# source.net
KiCad netlist of a schematic drawn in Altium Designer
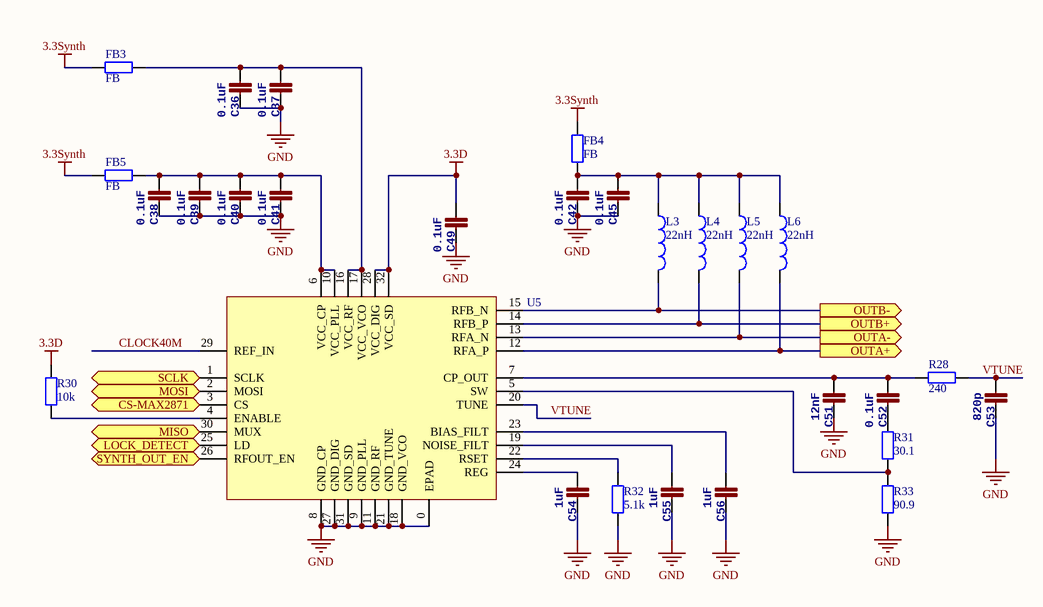
[diagram p0: source.SchDoc]

(export (version "E")
  (design (tool "Eeschema 10.0.6"))
  (components
    (comp (ref "C36")
      (value "0.1uF")
      (footprint "0402")
      (description "<b>Capacitor</b>\nStandard 0603 ceramic capacitor, and 0.1\" leaded capacitor.")
      (fields (field (name "PARTNO") "CC0402ZRY5V7BB104"))
      (libsource (lib "pixhawk2") (part "CAP0402-CAP"))
    )
    (comp (ref "C37")
      (value "0.1uF")
      (footprint "0402")
      (description "<b>Capacitor</b>\nStandard 0603 ceramic capacitor, and 0.1\" leaded capacitor.")
      (fields (field (name "PARTNO") "CC0402ZRY5V7BB104"))
      (libsource (lib "pixhawk2") (part "CAP0402-CAP"))
    )
    (comp (ref "C38")
      (value "0.1uF")
      (footprint "0402")
      (description "<b>Capacitor</b>\nStandard 0603 ceramic capacitor, and 0.1\" leaded capacitor.")
      (fields (field (name "PARTNO") "CC0402ZRY5V7BB104"))
      (libsource (lib "pixhawk2") (part "CAP0402-CAP"))
    )
    (comp (ref "C39")
      (value "0.1uF")
      (footprint "0402")
      (description "<b>Capacitor</b>\nStandard 0603 ceramic capacitor, and 0.1\" leaded capacitor.")
      (fields (field (name "PARTNO") "CC0402ZRY5V7BB104"))
      (libsource (lib "pixhawk2") (part "CAP0402-CAP"))
    )
    (comp (ref "C40")
      (value "0.1uF")
      (footprint "0402")
      (description "<b>Capacitor</b>\nStandard 0603 ceramic capacitor, and 0.1\" leaded capacitor.")
      (fields (field (name "PARTNO") "CC0402ZRY5V7BB104"))
      (libsource (lib "pixhawk2") (part "CAP0402-CAP"))
    )
    (comp (ref "C41")
      (value "0.1uF")
      (footprint "0402")
      (description "<b>Capacitor</b>\nStandard 0603 ceramic capacitor, and 0.1\" leaded capacitor.")
      (fields (field (name "PARTNO") "CC0402ZRY5V7BB104"))
      (libsource (lib "pixhawk2") (part "CAP0402-CAP"))
    )
    (comp (ref "C42")
      (value "0.1uF")
      (footprint "0402")
      (description "<b>Capacitor</b>\nStandard 0603 ceramic capacitor, and 0.1\" leaded capacitor.")
      (fields (field (name "PARTNO") "CC0402ZRY5V7BB104"))
      (libsource (lib "pixhawk2") (part "CAP0402-CAP"))
    )
    (comp (ref "C45")
      (value "0.1uF")
      (footprint "0402")
      (description "<b>Capacitor</b>\nStandard 0603 ceramic capacitor, and 0.1\" leaded capacitor.")
      (fields (field (name "PARTNO") "CC0402ZRY5V7BB104"))
      (libsource (lib "pixhawk2") (part "CAP0402-CAP"))
    )
    (comp (ref "C49")
      (value "0.1uF")
      (footprint "0402")
      (description "<b>Capacitor</b>\nStandard 0603 ceramic capacitor, and 0.1\" leaded capacitor.")
      (fields (field (name "PARTNO") "CC0402ZRY5V7BB104"))
      (libsource (lib "pixhawk2") (part "CAP0402-CAP"))
    )
    (comp (ref "C51")
      (value "12nF")
      (footprint "0402")
      (description "<b>Capacitor</b>\nStandard 0603 ceramic capacitor, and 0.1\" leaded capacitor.")
      (fields (field (name "PARTNO") "CC0402ZRY5V7BB104"))
      (libsource (lib "pixhawk2") (part "CAP0402-CAP"))
    )
    (comp (ref "C52")
      (value "0.1uF")
      (footprint "0402")
      (description "<b>Capacitor</b>\nStandard 0603 ceramic capacitor, and 0.1\" leaded capacitor.")
      (fields (field (name "PARTNO") "CC0402ZRY5V7BB104"))
      (libsource (lib "pixhawk2") (part "CAP0402-CAP"))
    )
    (comp (ref "C53")
      (value "820p")
      (footprint "0402")
      (description "<b>Capacitor</b>\nStandard 0603 ceramic capacitor, and 0.1\" leaded capacitor.")
      (fields (field (name "PARTNO") "CC0402ZRY5V7BB104"))
      (libsource (lib "pixhawk2") (part "CAP0402-CAP"))
    )
    (comp (ref "C54")
      (value "1uF")
      (footprint "0402")
      (description "<b>Capacitor</b>\nStandard 0603 ceramic capacitor, and 0.1\" leaded capacitor.")
      (fields (field (name "PARTNO") "CC0402ZRY5V7BB104"))
      (libsource (lib "pixhawk2") (part "CAP0402-CAP"))
    )
    (comp (ref "C55")
      (value "1uF")
      (footprint "0402")
      (description "<b>Capacitor</b>\nStandard 0603 ceramic capacitor, and 0.1\" leaded capacitor.")
      (fields (field (name "PARTNO") "CC0402ZRY5V7BB104"))
      (libsource (lib "pixhawk2") (part "CAP0402-CAP"))
    )
    (comp (ref "C56")
      (value "1uF")
      (footprint "0402")
      (description "<b>Capacitor</b>\nStandard 0603 ceramic capacitor, and 0.1\" leaded capacitor.")
      (fields (field (name "PARTNO") "CC0402ZRY5V7BB104"))
      (libsource (lib "pixhawk2") (part "CAP0402-CAP"))
    )
    (comp (ref "FB3")
      (value "FB")
      (footprint "0603")
      (description "Resistor")
      (fields (field (name "PUBLISHER") "Altium Limited"))
      (libsource (lib "") (part "Res2_2"))
    )
    (comp (ref "FB4")
      (value "FB")
      (footprint "0603")
      (description "Resistor")
      (fields (field (name "PUBLISHER") "Altium Limited"))
      (libsource (lib "Miscellaneous Devices") (part "Res2"))
    )
    (comp (ref "FB5")
      (value "FB")
      (footprint "0603")
      (description "Resistor")
      (fields (field (name "PUBLISHER") "Altium Limited"))
      (libsource (lib "") (part "Res2_2"))
    )
    (comp (ref "L3")
      (value "22nH")
      (footprint "0402")
      (description "Inductor")
      (fields (field (name "PUBLISHER") "Altium Limited"))
      (libsource (lib "Miscellaneous Devices") (part "Inductor"))
    )
    (comp (ref "L4")
      (value "22nH")
      (footprint "0402")
      (description "Inductor")
      (fields (field (name "PUBLISHER") "Altium Limited"))
      (libsource (lib "Miscellaneous Devices") (part "Inductor"))
    )
    (comp (ref "L5")
      (value "22nH")
      (footprint "0402")
      (description "Inductor")
      (fields (field (name "PUBLISHER") "Altium Limited"))
      (libsource (lib "Miscellaneous Devices") (part "Inductor"))
    )
    (comp (ref "L6")
      (value "22nH")
      (footprint "0402")
      (description "Inductor")
      (fields (field (name "PUBLISHER") "Altium Limited"))
      (libsource (lib "Miscellaneous Devices") (part "Inductor"))
    )
    (comp (ref "R28")
      (value "240")
      (footprint "0402")
      (description "Resistor")
      (fields (field (name "PUBLISHER") "Altium Limited"))
      (libsource (lib "") (part "Res2_2"))
    )
    (comp (ref "R30")
      (value "10k")
      (footprint "0402")
      (description "Resistor")
      (fields (field (name "PUBLISHER") "Altium Limited"))
      (libsource (lib "") (part "Res2_1"))
    )
    (comp (ref "R31")
      (value "30.1")
      (footprint "0402")
      (description "Resistor")
      (fields (field (name "PUBLISHER") "Altium Limited"))
      (libsource (lib "") (part "Res2_1"))
    )
    (comp (ref "R32")
      (value "5.1k")
      (footprint "0402")
      (description "Resistor")
      (fields (field (name "PUBLISHER") "Altium Limited"))
      (libsource (lib "") (part "Res2_1"))
    )
    (comp (ref "R33")
      (value "90.9")
      (footprint "0402")
      (description "Resistor")
      (fields (field (name "PUBLISHER") "Altium Limited"))
      (libsource (lib "") (part "Res2_1"))
    )
    (comp (ref "U5") (value "MAX2871") (footprint "MAX2871") (libsource (lib "F4SDR") (part "MAX2871")))
  )
  (nets
    (net (code "1") (name "/CLOCK40M") (class "Default")
      (node (ref "U5") (pin "29") (pinfunction "REF_IN_29") (pintype "passive"))
    )
    (net (code "2") (name "/CS-MAX2871") (class "Default")
      (node (ref "U5") (pin "3") (pinfunction "CS_3") (pintype "passive"))
    )
    (net (code "3") (name "/LOCK_DETECT") (class "Default")
      (node (ref "U5") (pin "25") (pinfunction "LD_25") (pintype "passive"))
    )
    (net (code "4") (name "/MISO") (class "Default")
      (node (ref "U5") (pin "30") (pinfunction "MUX_30") (pintype "passive"))
    )
    (net (code "5") (name "/MOSI") (class "Default")
      (node (ref "U5") (pin "2") (pinfunction "MOSI_2") (pintype "passive"))
    )
    (net (code "6") (name "/OUTA+") (class "Default")
      (node (ref "L6") (pin "2") (pinfunction "2_2") (pintype "passive"))
      (node (ref "U5") (pin "12") (pinfunction "RFA_P_12") (pintype "passive"))
    )
    (net (code "7") (name "/OUTA-") (class "Default")
      (node (ref "L5") (pin "2") (pinfunction "2_2") (pintype "passive"))
      (node (ref "U5") (pin "13") (pinfunction "RFA_N_13") (pintype "passive"))
    )
    (net (code "8") (name "/OUTB+") (class "Default")
      (node (ref "L4") (pin "2") (pinfunction "2_2") (pintype "passive"))
      (node (ref "U5") (pin "14") (pinfunction "RFB_P_14") (pintype "passive"))
    )
    (net (code "9") (name "/OUTB-") (class "Default")
      (node (ref "L3") (pin "2") (pinfunction "2_2") (pintype "passive"))
      (node (ref "U5") (pin "15") (pinfunction "RFB_N_15") (pintype "passive"))
    )
    (net (code "10") (name "/SCLK") (class "Default")
      (node (ref "U5") (pin "1") (pinfunction "SCLK_1") (pintype "passive"))
    )
    (net (code "11") (name "/SYNTH_OUT_EN") (class "Default")
      (node (ref "U5") (pin "26") (pinfunction "RFOUT_EN_26") (pintype "passive"))
    )
    (net (code "12") (name "/VTUNE") (class "Default")
      (node (ref "C53") (pin "1") (pinfunction "1_1") (pintype "passive"))
      (node (ref "R28") (pin "1") (pinfunction "1_1") (pintype "passive"))
      (node (ref "U5") (pin "20") (pinfunction "TUNE_20") (pintype "passive"))
    )
    (net (code "13") (name "3.3D") (class "Default")
      (node (ref "C49") (pin "1") (pinfunction "1_1") (pintype "passive"))
      (node (ref "R30") (pin "2") (pinfunction "2_2") (pintype "passive"))
      (node (ref "U5") (pin "28") (pinfunction "VCC_DIG_28") (pintype "passive"))
      (node (ref "U5") (pin "32") (pinfunction "VCC_SD_32") (pintype "passive"))
    )
    (net (code "14") (name "3.3Synth") (class "Default")
      (node (ref "FB3") (pin "2") (pinfunction "2_2") (pintype "passive"))
      (node (ref "FB4") (pin "1") (pinfunction "1_1") (pintype "passive"))
      (node (ref "FB5") (pin "2") (pinfunction "2_2") (pintype "passive"))
    )
    (net (code "15") (name "GND") (class "Default")
      (node (ref "C36") (pin "2") (pinfunction "2_2") (pintype "passive"))
      (node (ref "C37") (pin "2") (pinfunction "2_2") (pintype "passive"))
      (node (ref "C38") (pin "2") (pinfunction "2_2") (pintype "passive"))
      (node (ref "C39") (pin "2") (pinfunction "2_2") (pintype "passive"))
      (node (ref "C40") (pin "2") (pinfunction "2_2") (pintype "passive"))
      (node (ref "C41") (pin "2") (pinfunction "2_2") (pintype "passive"))
      (node (ref "C42") (pin "2") (pinfunction "2_2") (pintype "passive"))
      (node (ref "C45") (pin "2") (pinfunction "2_2") (pintype "passive"))
      (node (ref "C49") (pin "2") (pinfunction "2_2") (pintype "passive"))
      (node (ref "C51") (pin "2") (pinfunction "2_2") (pintype "passive"))
      (node (ref "C53") (pin "2") (pinfunction "2_2") (pintype "passive"))
      (node (ref "C54") (pin "2") (pinfunction "2_2") (pintype "passive"))
      (node (ref "C55") (pin "2") (pinfunction "2_2") (pintype "passive"))
      (node (ref "C56") (pin "2") (pinfunction "2_2") (pintype "passive"))
      (node (ref "R32") (pin "1") (pinfunction "1_1") (pintype "passive"))
      (node (ref "R33") (pin "1") (pinfunction "1_1") (pintype "passive"))
      (node (ref "U5") (pin "0") (pinfunction "EPAD_0") (pintype "passive"))
      (node (ref "U5") (pin "11") (pinfunction "GND_RF_11") (pintype "passive"))
      (node (ref "U5") (pin "18") (pinfunction "GND_VCO_18") (pintype "passive"))
      (node (ref "U5") (pin "21") (pinfunction "GND_TUNE_21") (pintype "passive"))
      (node (ref "U5") (pin "27") (pinfunction "GND_DIG_27") (pintype "passive"))
      (node (ref "U5") (pin "31") (pinfunction "GND_SD_31") (pintype "passive"))
      (node (ref "U5") (pin "8") (pinfunction "GND_CP_8") (pintype "passive"))
      (node (ref "U5") (pin "9") (pinfunction "GND_PLL_9") (pintype "passive"))
    )
    (net (code "16") (name "Net-(C42-Pad1)") (class "Default")
      (node (ref "C42") (pin "1") (pinfunction "1_1") (pintype "passive"))
      (node (ref "C45") (pin "1") (pinfunction "1_1") (pintype "passive"))
      (node (ref "FB4") (pin "2") (pinfunction "2_2") (pintype "passive"))
      (node (ref "L3") (pin "1") (pinfunction "1_1") (pintype "passive"))
      (node (ref "L4") (pin "1") (pinfunction "1_1") (pintype "passive"))
      (node (ref "L5") (pin "1") (pinfunction "1_1") (pintype "passive"))
      (node (ref "L6") (pin "1") (pinfunction "1_1") (pintype "passive"))
    )
    (net (code "17") (name "Net-(C52-Pad2)") (class "Default")
      (node (ref "C52") (pin "2") (pinfunction "2_2") (pintype "passive"))
      (node (ref "R31") (pin "2") (pinfunction "2_2") (pintype "passive"))
    )
    (net (code "18") (name "Net-(U5-BIAS_FILT)") (class "Default")
      (node (ref "C56") (pin "1") (pinfunction "1_1") (pintype "passive"))
      (node (ref "U5") (pin "23") (pinfunction "BIAS_FILT_23") (pintype "passive"))
    )
    (net (code "19") (name "Net-(U5-CP_OUT)") (class "Default")
      (node (ref "C51") (pin "1") (pinfunction "1_1") (pintype "passive"))
      (node (ref "C52") (pin "1") (pinfunction "1_1") (pintype "passive"))
      (node (ref "R28") (pin "2") (pinfunction "2_2") (pintype "passive"))
      (node (ref "U5") (pin "7") (pinfunction "CP_OUT_7") (pintype "passive"))
    )
    (net (code "20") (name "Net-(U5-ENABLE)") (class "Default")
      (node (ref "R30") (pin "1") (pinfunction "1_1") (pintype "passive"))
      (node (ref "U5") (pin "4") (pinfunction "ENABLE_4") (pintype "passive"))
    )
    (net (code "21") (name "Net-(U5-NOISE_FILT)") (class "Default")
      (node (ref "C55") (pin "1") (pinfunction "1_1") (pintype "passive"))
      (node (ref "U5") (pin "19") (pinfunction "NOISE_FILT_19") (pintype "passive"))
    )
    (net (code "22") (name "Net-(U5-REG)") (class "Default")
      (node (ref "C54") (pin "1") (pinfunction "1_1") (pintype "passive"))
      (node (ref "U5") (pin "24") (pinfunction "REG_24") (pintype "passive"))
    )
    (net (code "23") (name "Net-(U5-RSET)") (class "Default")
      (node (ref "R32") (pin "2") (pinfunction "2_2") (pintype "passive"))
      (node (ref "U5") (pin "22") (pinfunction "RSET_22") (pintype "passive"))
    )
    (net (code "24") (name "Net-(U5-SW)") (class "Default")
      (node (ref "R31") (pin "1") (pinfunction "1_1") (pintype "passive"))
      (node (ref "R33") (pin "2") (pinfunction "2_2") (pintype "passive"))
      (node (ref "U5") (pin "5") (pinfunction "SW_5") (pintype "passive"))
    )
    (net (code "25") (name "Net-(U5-VCC_CP)") (class "Default")
      (node (ref "C38") (pin "1") (pinfunction "1_1") (pintype "passive"))
      (node (ref "C39") (pin "1") (pinfunction "1_1") (pintype "passive"))
      (node (ref "C40") (pin "1") (pinfunction "1_1") (pintype "passive"))
      (node (ref "C41") (pin "1") (pinfunction "1_1") (pintype "passive"))
      (node (ref "FB5") (pin "1") (pinfunction "1_1") (pintype "passive"))
      (node (ref "U5") (pin "10") (pinfunction "VCC_PLL_10") (pintype "passive"))
      (node (ref "U5") (pin "6") (pinfunction "VCC_CP_6") (pintype "passive"))
    )
    (net (code "26") (name "Net-(U5-VCC_RF)") (class "Default")
      (node (ref "C36") (pin "1") (pinfunction "1_1") (pintype "passive"))
      (node (ref "C37") (pin "1") (pinfunction "1_1") (pintype "passive"))
      (node (ref "FB3") (pin "1") (pinfunction "1_1") (pintype "passive"))
      (node (ref "U5") (pin "16") (pinfunction "VCC_RF_16") (pintype "passive"))
      (node (ref "U5") (pin "17") (pinfunction "VCC_VCO_17") (pintype "passive"))
    )
  )
)
